# 07_USB.net
KiCad netlist of a schematic drawn in Altium Designer
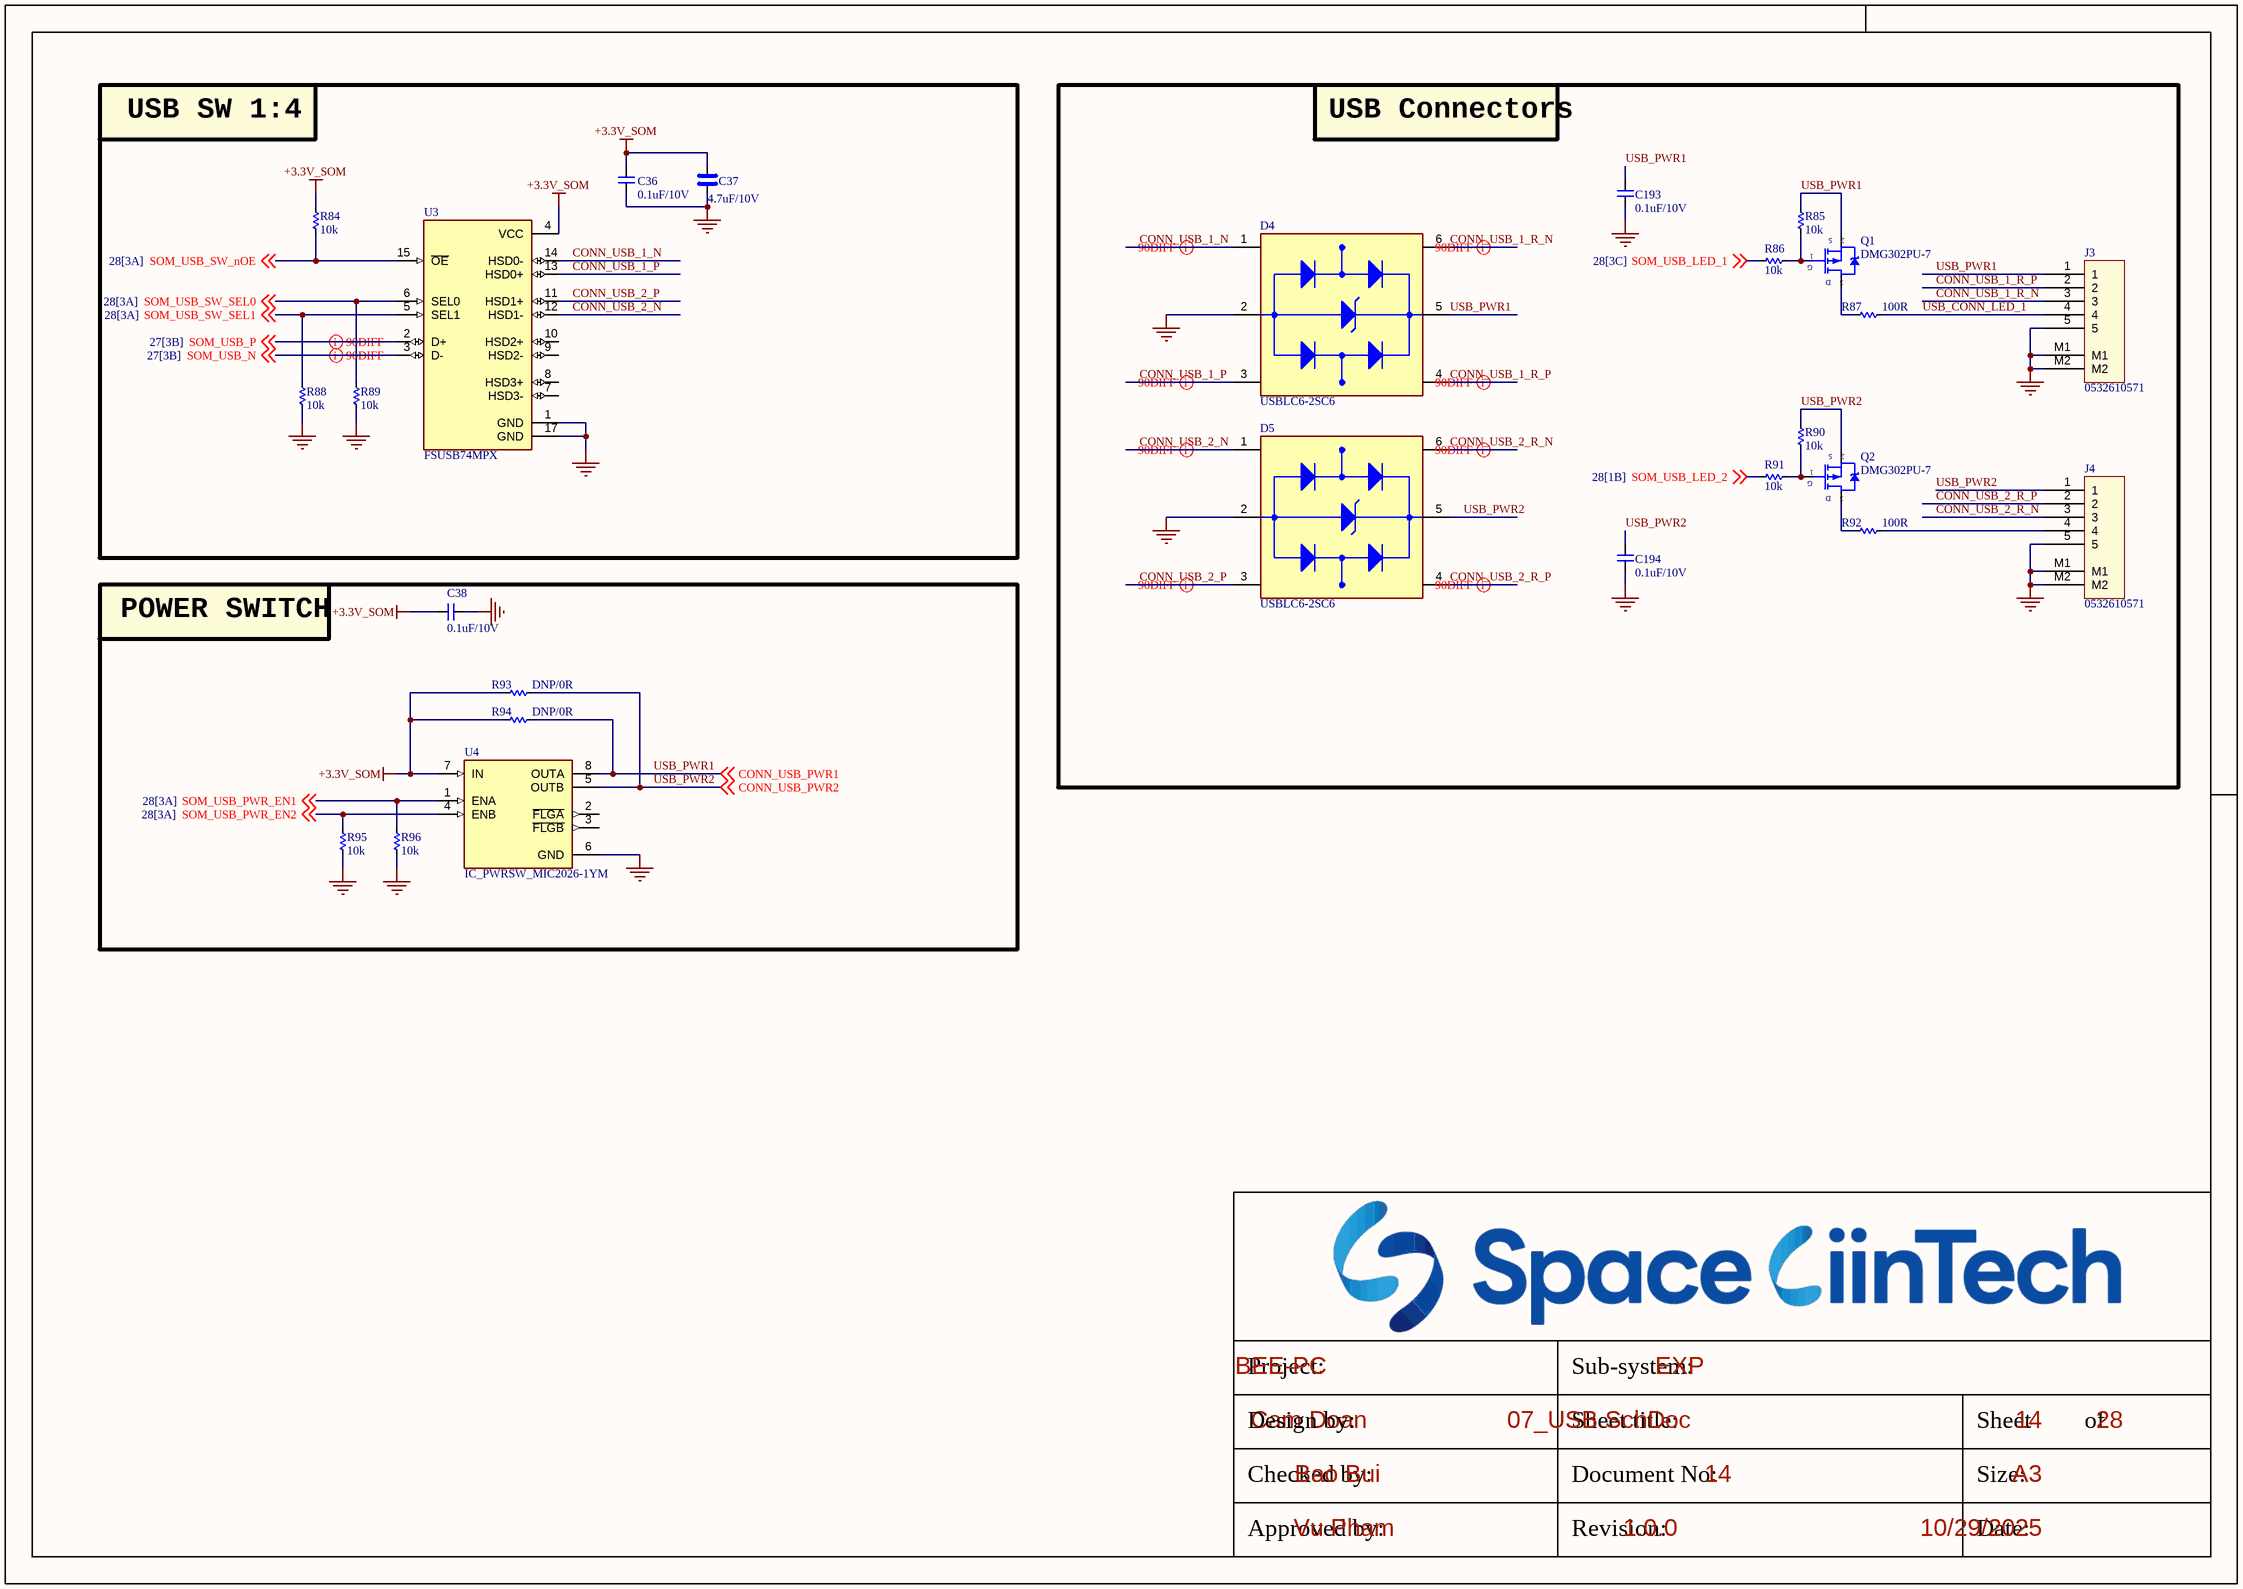
[diagram p0: 07_USB.SchDoc]

(export (version "E")
  (design (tool "Eeschema 10.0.6"))
  (components
    (comp (ref "C36")
      (value "0.1uF/10V")
      (footprint "CAP_C_1005X60")
      (description "CAP CHIP")
      (libsource (lib "LABLIB") (part "_CAP_C_2"))
    )
    (comp (ref "C37")
      (value "4.7uF/10V")
      (footprint "CAP_C_1005X60")
      (description "CAP CHIP High Value")
      (libsource (lib "LABLIB") (part "_CAP_C_High_2"))
    )
    (comp (ref "C38")
      (value "0.1uF/10V")
      (footprint "CAP_C_1005X60")
      (description "CAP CHIP")
      (libsource (lib "LABLIB") (part "_CAP_C_2"))
    )
    (comp (ref "C193")
      (value "0.1uF/10V")
      (footprint "CAP_C_1005X60")
      (description "CAP CHIP")
      (libsource (lib "LABLIB") (part "_CAP_C_2"))
    )
    (comp (ref "C194")
      (value "0.1uF/10V")
      (footprint "CAP_C_1005X60")
      (description "CAP CHIP")
      (libsource (lib "LABLIB") (part "_CAP_C_2"))
    )
    (comp (ref "D4")
      (value "USBLC6-2SC6")
      (footprint "SOT95P280X145-6N")
      (description "17V Clamp 5A (8/20Âµs) Ipp Tvs Diode Surface Mount SOT-23-6")
      (fields (field (name "MF") "STMicroelectronics"))
      (libsource (lib "USBLC6-2SC6") (part "USBLC6-2SC6"))
    )
    (comp (ref "D5")
      (value "USBLC6-2SC6")
      (footprint "SOT95P280X145-6N")
      (description "17V Clamp 5A (8/20Âµs) Ipp Tvs Diode Surface Mount SOT-23-6")
      (fields (field (name "MF") "STMicroelectronics"))
      (libsource (lib "USBLC6-2SC6") (part "USBLC6-2SC6"))
    )
    (comp (ref "J3")
      (value "0532610571")
      (footprint "MOLEX_0532610571")
      (libsource (lib "LABLIB") (part "Header 5x1_2M"))
    )
    (comp (ref "J4")
      (value "0532610571")
      (footprint "MOLEX_0532610571")
      (libsource (lib "LABLIB") (part "Header 5x1_2M"))
    )
    (comp (ref "Q1")
      (value "DMG302PU-7")
      (footprint "SOT95P240X120-3N")
      (libsource (lib "LABLIB") (part "MOSFET_P_GSD"))
    )
    (comp (ref "Q2")
      (value "DMG302PU-7")
      (footprint "SOT95P240X120-3N")
      (libsource (lib "LABLIB") (part "MOSFET_P_GSD"))
    )
    (comp (ref "R84")
      (value "10k")
      (footprint "RES_C_1005X40")
      (description "RES")
      (libsource (lib "LABLIB") (part "_RES_B_2"))
    )
    (comp (ref "R85")
      (value "10k")
      (footprint "RES_C_1005X40")
      (description "RES")
      (libsource (lib "LABLIB") (part "_RES_B_2"))
    )
    (comp (ref "R86")
      (value "10k")
      (footprint "RES_C_1005X40")
      (description "RES")
      (libsource (lib "LABLIB") (part "_RES_B_2"))
    )
    (comp (ref "R87")
      (value "100R")
      (footprint "RES_C_1005X40")
      (description "RES")
      (libsource (lib "LABLIB") (part "_RES_B_2"))
    )
    (comp (ref "R88")
      (value "10k")
      (footprint "RES_C_1005X40")
      (description "RES")
      (libsource (lib "LABLIB") (part "_RES_B_2"))
    )
    (comp (ref "R89")
      (value "10k")
      (footprint "RES_C_1005X40")
      (description "RES")
      (libsource (lib "LABLIB") (part "_RES_B_2"))
    )
    (comp (ref "R90")
      (value "10k")
      (footprint "RES_C_1005X40")
      (description "RES")
      (libsource (lib "LABLIB") (part "_RES_B_2"))
    )
    (comp (ref "R91")
      (value "10k")
      (footprint "RES_C_1005X40")
      (description "RES")
      (libsource (lib "LABLIB") (part "_RES_B_2"))
    )
    (comp (ref "R92")
      (value "100R")
      (footprint "RES_C_1005X40")
      (description "RES")
      (libsource (lib "LABLIB") (part "_RES_B_2"))
    )
    (comp (ref "R93")
      (value "DNP/0R")
      (footprint "RES_C_1005X40")
      (description "RES")
      (libsource (lib "LABLIB") (part "_RES_B_2"))
    )
    (comp (ref "R94")
      (value "DNP/0R")
      (footprint "RES_C_1005X40")
      (description "RES")
      (libsource (lib "LABLIB") (part "_RES_B_2"))
    )
    (comp (ref "R95")
      (value "10k")
      (footprint "RES_C_1005X40")
      (description "RES")
      (libsource (lib "LABLIB") (part "_RES_B_2"))
    )
    (comp (ref "R96")
      (value "10k")
      (footprint "RES_C_1005X40")
      (description "RES")
      (libsource (lib "LABLIB") (part "_RES_B_2"))
    )
    (comp (ref "U3")
      (value "FSUSB74MPX")
      (footprint "QFN50P300X300X80-17N")
      (description "USB Switch IC 1 Channel 16-MLP (3x3)")
      (fields (field (name "MF") "ON Semiconductor"))
      (libsource (lib "LABLIB") (part "IC_USB_SW_FSUSB74MPX"))
    )
    (comp (ref "U4")
      (value "IC_PWRSW_MIC2026-1YM")
      (footprint "SOIC127P602X173-8N")
      (description "Power Switch/Driver 1:2 N-Channel 1.25A 8-SOIC")
      (fields (field (name "MF") "Microchip") (field (name "MP") "MIC2026-1YM"))
      (libsource (lib "LABLIB") (part "IC_PWRSW_MIC2026-1YM"))
    )
  )
  (nets
    (net (code "1") (name "+3.3V_SOM") (class "Default")
      (node (ref "C36") (pin "2") (pinfunction "2_2") (pintype "passive"))
      (node (ref "C37") (pin "2") (pinfunction "2_2") (pintype "passive"))
      (node (ref "C38") (pin "2") (pinfunction "2_2") (pintype "passive"))
      (node (ref "R84") (pin "1") (pinfunction "1_1") (pintype "passive"))
      (node (ref "R93") (pin "2") (pinfunction "2_2") (pintype "passive"))
      (node (ref "R94") (pin "2") (pinfunction "2_2") (pintype "passive"))
      (node (ref "U3") (pin "4") (pinfunction "VCC_4") (pintype "power_in"))
      (node (ref "U4") (pin "7") (pinfunction "IN_7") (pintype "input"))
    )
    (net (code "2") (name "/CONN_USB_1_N") (class "Default")
      (node (ref "D4") (pin "1") (pinfunction "I/O1_IN_1") (pintype "passive"))
      (node (ref "U3") (pin "14") (pinfunction "HSD0-_14") (pintype "bidirectional"))
    )
    (net (code "3") (name "/CONN_USB_1_P") (class "Default")
      (node (ref "D4") (pin "3") (pinfunction "I/O2_IN_3") (pintype "passive"))
      (node (ref "U3") (pin "13") (pinfunction "HSD0+_13") (pintype "bidirectional"))
    )
    (net (code "4") (name "/CONN_USB_1_R_N") (class "Default")
      (node (ref "D4") (pin "6") (pinfunction "I/O1_OUT_6") (pintype "passive"))
      (node (ref "J3") (pin "3") (pinfunction "3_3") (pintype "passive"))
    )
    (net (code "5") (name "/CONN_USB_1_R_P") (class "Default")
      (node (ref "D4") (pin "4") (pinfunction "I/O2_OUT_4") (pintype "passive"))
      (node (ref "J3") (pin "2") (pinfunction "2_2") (pintype "passive"))
    )
    (net (code "6") (name "/CONN_USB_2_N") (class "Default")
      (node (ref "D5") (pin "1") (pinfunction "I/O1_IN_1") (pintype "passive"))
      (node (ref "U3") (pin "12") (pinfunction "HSD1-_12") (pintype "bidirectional"))
    )
    (net (code "7") (name "/CONN_USB_2_P") (class "Default")
      (node (ref "D5") (pin "3") (pinfunction "I/O2_IN_3") (pintype "passive"))
      (node (ref "U3") (pin "11") (pinfunction "HSD1+_11") (pintype "bidirectional"))
    )
    (net (code "8") (name "/CONN_USB_2_R_N") (class "Default")
      (node (ref "D5") (pin "6") (pinfunction "I/O1_OUT_6") (pintype "passive"))
      (node (ref "J4") (pin "3") (pinfunction "3_3") (pintype "passive"))
    )
    (net (code "9") (name "/CONN_USB_2_R_P") (class "Default")
      (node (ref "D5") (pin "4") (pinfunction "I/O2_OUT_4") (pintype "passive"))
      (node (ref "J4") (pin "2") (pinfunction "2_2") (pintype "passive"))
    )
    (net (code "10") (name "/USB_CONN_LED_1") (class "Default")
      (node (ref "J3") (pin "4") (pinfunction "4_4") (pintype "passive"))
      (node (ref "R87") (pin "2") (pinfunction "2_2") (pintype "passive"))
    )
    (net (code "11") (name "CONN_USB_PWR1") (class "Default")
      (node (ref "C193") (pin "2") (pinfunction "2_2") (pintype "passive"))
      (node (ref "D4") (pin "5") (pinfunction "VBUS_5") (pintype "power_in"))
      (node (ref "J3") (pin "1") (pinfunction "1_1") (pintype "passive"))
      (node (ref "Q1") (pin "2") (pinfunction "S_2") (pintype "passive"))
      (node (ref "R85") (pin "1") (pinfunction "1_1") (pintype "passive"))
      (node (ref "R94") (pin "1") (pinfunction "1_1") (pintype "passive"))
      (node (ref "U4") (pin "8") (pinfunction "OUTA_8") (pintype "passive"))
    )
    (net (code "12") (name "CONN_USB_PWR2") (class "Default")
      (node (ref "C194") (pin "2") (pinfunction "2_2") (pintype "passive"))
      (node (ref "D5") (pin "5") (pinfunction "VBUS_5") (pintype "power_in"))
      (node (ref "J4") (pin "1") (pinfunction "1_1") (pintype "passive"))
      (node (ref "Q2") (pin "2") (pinfunction "S_2") (pintype "passive"))
      (node (ref "R90") (pin "1") (pinfunction "1_1") (pintype "passive"))
      (node (ref "R93") (pin "1") (pinfunction "1_1") (pintype "passive"))
      (node (ref "U4") (pin "5") (pinfunction "OUTB_5") (pintype "passive"))
    )
    (net (code "13") (name "GND") (class "Default")
      (node (ref "C193") (pin "1") (pinfunction "1_1") (pintype "passive"))
      (node (ref "C194") (pin "1") (pinfunction "1_1") (pintype "passive"))
      (node (ref "C36") (pin "1") (pinfunction "1_1") (pintype "passive"))
      (node (ref "C37") (pin "1") (pinfunction "1_1") (pintype "passive"))
      (node (ref "C38") (pin "1") (pinfunction "1_1") (pintype "passive"))
      (node (ref "D4") (pin "2") (pinfunction "GND_2") (pintype "power_in"))
      (node (ref "D5") (pin "2") (pinfunction "GND_2") (pintype "power_in"))
      (node (ref "J3") (pin "5") (pinfunction "5_5") (pintype "passive"))
      (node (ref "J3") (pin "M1") (pinfunction "M1_M1") (pintype "passive"))
      (node (ref "J3") (pin "M2") (pinfunction "M2_M2") (pintype "passive"))
      (node (ref "J4") (pin "5") (pinfunction "5_5") (pintype "passive"))
      (node (ref "J4") (pin "M1") (pinfunction "M1_M1") (pintype "passive"))
      (node (ref "J4") (pin "M2") (pinfunction "M2_M2") (pintype "passive"))
      (node (ref "R88") (pin "2") (pinfunction "2_2") (pintype "passive"))
      (node (ref "R89") (pin "2") (pinfunction "2_2") (pintype "passive"))
      (node (ref "R95") (pin "2") (pinfunction "2_2") (pintype "passive"))
      (node (ref "R96") (pin "2") (pinfunction "2_2") (pintype "passive"))
      (node (ref "U3") (pin "1") (pinfunction "GND_1") (pintype "power_in"))
      (node (ref "U3") (pin "17") (pinfunction "GND_17") (pintype "power_in"))
      (node (ref "U4") (pin "6") (pinfunction "GND_6") (pintype "power_in"))
    )
    (net (code "14") (name "Net-(J4-Pad4)") (class "Default")
      (node (ref "J4") (pin "4") (pinfunction "4_4") (pintype "passive"))
      (node (ref "R92") (pin "2") (pinfunction "2_2") (pintype "passive"))
    )
    (net (code "15") (name "Net-(Q1-D)") (class "Default")
      (node (ref "Q1") (pin "3") (pinfunction "D_3") (pintype "passive"))
      (node (ref "R87") (pin "1") (pinfunction "1_1") (pintype "passive"))
    )
    (net (code "16") (name "Net-(Q1-G)") (class "Default")
      (node (ref "Q1") (pin "1") (pinfunction "G_1") (pintype "passive"))
      (node (ref "R85") (pin "2") (pinfunction "2_2") (pintype "passive"))
      (node (ref "R86") (pin "2") (pinfunction "2_2") (pintype "passive"))
    )
    (net (code "17") (name "Net-(Q2-D)") (class "Default")
      (node (ref "Q2") (pin "3") (pinfunction "D_3") (pintype "passive"))
      (node (ref "R92") (pin "1") (pinfunction "1_1") (pintype "passive"))
    )
    (net (code "18") (name "Net-(Q2-G)") (class "Default")
      (node (ref "Q2") (pin "1") (pinfunction "G_1") (pintype "passive"))
      (node (ref "R90") (pin "2") (pinfunction "2_2") (pintype "passive"))
      (node (ref "R91") (pin "2") (pinfunction "2_2") (pintype "passive"))
    )
    (net (code "19") (name "SOM_USB_LED_1") (class "Default")
      (node (ref "R86") (pin "1") (pinfunction "1_1") (pintype "passive"))
    )
    (net (code "20") (name "SOM_USB_LED_2") (class "Default")
      (node (ref "R91") (pin "1") (pinfunction "1_1") (pintype "passive"))
    )
    (net (code "21") (name "SOM_USB_N") (class "Default")
      (node (ref "U3") (pin "3") (pinfunction "D-_3") (pintype "bidirectional"))
    )
    (net (code "22") (name "SOM_USB_P") (class "Default")
      (node (ref "U3") (pin "2") (pinfunction "D+_2") (pintype "bidirectional"))
    )
    (net (code "23") (name "SOM_USB_PWR_EN1") (class "Default")
      (node (ref "R96") (pin "1") (pinfunction "1_1") (pintype "passive"))
      (node (ref "U4") (pin "1") (pinfunction "ENA_1") (pintype "input"))
    )
    (net (code "24") (name "SOM_USB_PWR_EN2") (class "Default")
      (node (ref "R95") (pin "1") (pinfunction "1_1") (pintype "passive"))
      (node (ref "U4") (pin "4") (pinfunction "ENB_4") (pintype "input"))
    )
    (net (code "25") (name "SOM_USB_SW_SEL0") (class "Default")
      (node (ref "R89") (pin "1") (pinfunction "1_1") (pintype "passive"))
      (node (ref "U3") (pin "6") (pinfunction "SEL0_6") (pintype "input"))
    )
    (net (code "26") (name "SOM_USB_SW_SEL1") (class "Default")
      (node (ref "R88") (pin "1") (pinfunction "1_1") (pintype "passive"))
      (node (ref "U3") (pin "5") (pinfunction "SEL1_5") (pintype "input"))
    )
    (net (code "27") (name "SOM_USB_SW_nOE") (class "Default")
      (node (ref "R84") (pin "2") (pinfunction "2_2") (pintype "passive"))
      (node (ref "U3") (pin "15") (pinfunction "~{OE}_15") (pintype "input"))
    )
    (net (code "28") (name "unconnected-(U3-HSD2+-Pad10)") (class "Default")
      (node (ref "U3") (pin "10") (pinfunction "HSD2+_10") (pintype "bidirectional"))
    )
    (net (code "29") (name "unconnected-(U3-HSD2--Pad9)") (class "Default")
      (node (ref "U3") (pin "9") (pinfunction "HSD2-_9") (pintype "bidirectional"))
    )
    (net (code "30") (name "unconnected-(U3-HSD3+-Pad8)") (class "Default")
      (node (ref "U3") (pin "8") (pinfunction "HSD3+_8") (pintype "bidirectional"))
    )
    (net (code "31") (name "unconnected-(U3-HSD3--Pad7)") (class "Default")
      (node (ref "U3") (pin "7") (pinfunction "HSD3-_7") (pintype "bidirectional"))
    )
    (net (code "32") (name "unconnected-(U4-~{FLGA}-Pad2)") (class "Default")
      (node (ref "U4") (pin "2") (pinfunction "~{FLGA}_2") (pintype "output"))
    )
    (net (code "33") (name "unconnected-(U4-~{FLGB}-Pad3)") (class "Default")
      (node (ref "U4") (pin "3") (pinfunction "~{FLGB}_3") (pintype "output"))
    )
  )
)
